# BumpSensors.net
KiCad netlist of a schematic drawn in Altium Designer
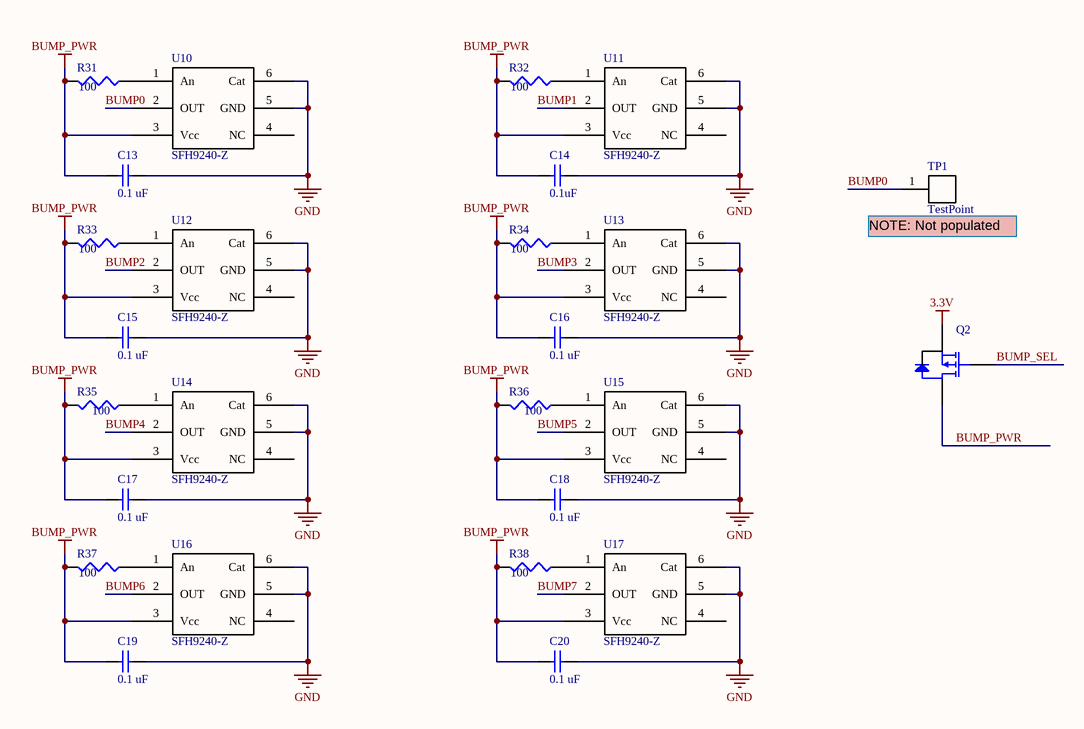
[diagram p0: BumpSensors.SchDoc]

(export (version "E")
  (design (tool "Eeschema 10.0.6"))
  (components
    (comp (ref "C13")
      (value "0.1 uF")
      (footprint "CAPC1005L")
      (description "Capacitor (Semiconductor SIM Model)")
      (fields (field (name "Comment") "Cap Semi") (field (name "PUBLISHER") "Altium Limited"))
      (libsource (lib "Miscellaneous Devices") (part "Cap Semi"))
    )
    (comp (ref "C14")
      (value "0.1uF")
      (footprint "CAPC1005L")
      (description "Capacitor (Semiconductor SIM Model)")
      (fields (field (name "Comment") "Cap Semi") (field (name "PUBLISHER") "Altium Limited"))
      (libsource (lib "Miscellaneous Devices") (part "Cap Semi"))
    )
    (comp (ref "C15")
      (value "0.1 uF")
      (footprint "CAPC1005L")
      (description "Capacitor (Semiconductor SIM Model)")
      (fields (field (name "Comment") "Cap Semi") (field (name "PUBLISHER") "Altium Limited"))
      (libsource (lib "Miscellaneous Devices") (part "Cap Semi"))
    )
    (comp (ref "C16")
      (value "0.1 uF")
      (footprint "CAPC1005L")
      (description "Capacitor (Semiconductor SIM Model)")
      (fields (field (name "Comment") "Cap Semi") (field (name "PUBLISHER") "Altium Limited"))
      (libsource (lib "Miscellaneous Devices") (part "Cap Semi"))
    )
    (comp (ref "C17")
      (value "0.1 uF")
      (footprint "CAPC1005L")
      (description "Capacitor (Semiconductor SIM Model)")
      (fields (field (name "Comment") "Cap Semi") (field (name "PUBLISHER") "Altium Limited"))
      (libsource (lib "Miscellaneous Devices") (part "Cap Semi"))
    )
    (comp (ref "C18")
      (value "0.1 uF")
      (footprint "CAPC1005L")
      (description "Capacitor (Semiconductor SIM Model)")
      (fields (field (name "Comment") "Cap Semi") (field (name "PUBLISHER") "Altium Limited"))
      (libsource (lib "Miscellaneous Devices") (part "Cap Semi"))
    )
    (comp (ref "C19")
      (value "0.1 uF")
      (footprint "CAPC1005L")
      (description "Capacitor (Semiconductor SIM Model)")
      (fields (field (name "Comment") "Cap Semi") (field (name "PUBLISHER") "Altium Limited"))
      (libsource (lib "Miscellaneous Devices") (part "Cap Semi"))
    )
    (comp (ref "C20")
      (value "0.1 uF")
      (footprint "CAPC1005L")
      (description "Capacitor (Semiconductor SIM Model)")
      (fields (field (name "Comment") "Cap Semi") (field (name "PUBLISHER") "Altium Limited"))
      (libsource (lib "Miscellaneous Devices") (part "Cap Semi"))
    )
    (comp (ref "Q2") (value "P-Mosfet") (footprint "SOT-23") (libsource (lib "mrone") (part "P-Mosfet")))
    (comp (ref "R31")
      (value "100")
      (footprint "RESC1608L")
      (description "Resistor")
      (fields (field (name "Comment") "Res3") (field (name "PUBLISHER") "Altium Limited"))
      (libsource (lib "Miscellaneous Devices") (part "Res3"))
    )
    (comp (ref "R32")
      (value "100")
      (footprint "RESC1608L")
      (description "Resistor")
      (fields (field (name "Comment") "Res3") (field (name "PUBLISHER") "Altium Limited"))
      (libsource (lib "Miscellaneous Devices") (part "Res3"))
    )
    (comp (ref "R33")
      (value "100")
      (footprint "RESC1608L")
      (description "Resistor")
      (fields (field (name "Comment") "Res3") (field (name "PUBLISHER") "Altium Limited"))
      (libsource (lib "Miscellaneous Devices") (part "Res3"))
    )
    (comp (ref "R34")
      (value "100")
      (footprint "RESC1608L")
      (description "Resistor")
      (fields (field (name "Comment") "Res3") (field (name "PUBLISHER") "Altium Limited"))
      (libsource (lib "Miscellaneous Devices") (part "Res3"))
    )
    (comp (ref "R35")
      (value "100")
      (footprint "RESC1608L")
      (description "Resistor")
      (fields (field (name "Comment") "Res3") (field (name "PUBLISHER") "Altium Limited"))
      (libsource (lib "Miscellaneous Devices") (part "Res3"))
    )
    (comp (ref "R36")
      (value "100")
      (footprint "RESC1608L")
      (description "Resistor")
      (fields (field (name "Comment") "Res3") (field (name "PUBLISHER") "Altium Limited"))
      (libsource (lib "Miscellaneous Devices") (part "Res3"))
    )
    (comp (ref "R37")
      (value "100")
      (footprint "RESC1608L")
      (description "Resistor")
      (fields (field (name "Comment") "Res3") (field (name "PUBLISHER") "Altium Limited"))
      (libsource (lib "Miscellaneous Devices") (part "Res3"))
    )
    (comp (ref "R38")
      (value "100")
      (footprint "RESC1608L")
      (description "Resistor")
      (fields (field (name "Comment") "Res3") (field (name "PUBLISHER") "Altium Limited"))
      (libsource (lib "Miscellaneous Devices") (part "Res3"))
    )
    (comp (ref "TP1")
      (value "TestPoint")
      (footprint "TestPoint")
      (libsource (lib "mrone") (part "TestPoint"))
    )
    (comp (ref "U10")
      (value "SFH9240-Z")
      (footprint "SFH9240-Z")
      (libsource (lib "mrone") (part "SFH9240-Z"))
    )
    (comp (ref "U11")
      (value "SFH9240-Z")
      (footprint "SFH9240-Z")
      (libsource (lib "mrone") (part "SFH9240-Z"))
    )
    (comp (ref "U12")
      (value "SFH9240-Z")
      (footprint "SFH9240-Z")
      (libsource (lib "mrone") (part "SFH9240-Z"))
    )
    (comp (ref "U13")
      (value "SFH9240-Z")
      (footprint "SFH9240-Z")
      (libsource (lib "mrone") (part "SFH9240-Z"))
    )
    (comp (ref "U14")
      (value "SFH9240-Z")
      (footprint "SFH9240-Z")
      (libsource (lib "mrone") (part "SFH9240-Z"))
    )
    (comp (ref "U15")
      (value "SFH9240-Z")
      (footprint "SFH9240-Z")
      (libsource (lib "mrone") (part "SFH9240-Z"))
    )
    (comp (ref "U16")
      (value "SFH9240-Z")
      (footprint "SFH9240-Z")
      (libsource (lib "mrone") (part "SFH9240-Z"))
    )
    (comp (ref "U17")
      (value "SFH9240-Z")
      (footprint "SFH9240-Z")
      (libsource (lib "mrone") (part "SFH9240-Z"))
    )
  )
  (nets
    (net (code "1") (name "/BUMP0") (class "Default")
      (node (ref "TP1") (pin "1") (pintype "passive"))
      (node (ref "U10") (pin "2") (pinfunction "OUT_2") (pintype "passive"))
    )
    (net (code "2") (name "/BUMP1") (class "Default")
      (node (ref "U11") (pin "2") (pinfunction "OUT_2") (pintype "passive"))
    )
    (net (code "3") (name "/BUMP2") (class "Default")
      (node (ref "U12") (pin "2") (pinfunction "OUT_2") (pintype "passive"))
    )
    (net (code "4") (name "/BUMP3") (class "Default")
      (node (ref "U13") (pin "2") (pinfunction "OUT_2") (pintype "passive"))
    )
    (net (code "5") (name "/BUMP4") (class "Default")
      (node (ref "U14") (pin "2") (pinfunction "OUT_2") (pintype "passive"))
    )
    (net (code "6") (name "/BUMP5") (class "Default")
      (node (ref "U15") (pin "2") (pinfunction "OUT_2") (pintype "passive"))
    )
    (net (code "7") (name "/BUMP6") (class "Default")
      (node (ref "U16") (pin "2") (pinfunction "OUT_2") (pintype "passive"))
    )
    (net (code "8") (name "/BUMP7") (class "Default")
      (node (ref "U17") (pin "2") (pinfunction "OUT_2") (pintype "passive"))
    )
    (net (code "9") (name "/BUMP_SEL") (class "Default")
      (node (ref "Q2") (pin "1") (pinfunction "G_1") (pintype "passive"))
    )
    (net (code "10") (name "3.3V") (class "Default")
      (node (ref "Q2") (pin "2") (pinfunction "S_2") (pintype "passive"))
    )
    (net (code "11") (name "BUMP_PWR") (class "Default")
      (node (ref "C13") (pin "2") (pinfunction "2_2") (pintype "passive"))
      (node (ref "C14") (pin "2") (pinfunction "2_2") (pintype "passive"))
      (node (ref "C15") (pin "2") (pinfunction "2_2") (pintype "passive"))
      (node (ref "C16") (pin "2") (pinfunction "2_2") (pintype "passive"))
      (node (ref "C17") (pin "2") (pinfunction "2_2") (pintype "passive"))
      (node (ref "C18") (pin "2") (pinfunction "2_2") (pintype "passive"))
      (node (ref "C19") (pin "2") (pinfunction "2_2") (pintype "passive"))
      (node (ref "C20") (pin "2") (pinfunction "2_2") (pintype "passive"))
      (node (ref "Q2") (pin "3") (pinfunction "D_3") (pintype "passive"))
      (node (ref "R31") (pin "2") (pinfunction "2_2") (pintype "passive"))
      (node (ref "R32") (pin "2") (pinfunction "2_2") (pintype "passive"))
      (node (ref "R33") (pin "2") (pinfunction "2_2") (pintype "passive"))
      (node (ref "R34") (pin "2") (pinfunction "2_2") (pintype "passive"))
      (node (ref "R35") (pin "2") (pinfunction "2_2") (pintype "passive"))
      (node (ref "R36") (pin "2") (pinfunction "2_2") (pintype "passive"))
      (node (ref "R37") (pin "2") (pinfunction "2_2") (pintype "passive"))
      (node (ref "R38") (pin "2") (pinfunction "2_2") (pintype "passive"))
      (node (ref "U10") (pin "3") (pinfunction "Vcc_3") (pintype "passive"))
      (node (ref "U11") (pin "3") (pinfunction "Vcc_3") (pintype "passive"))
      (node (ref "U12") (pin "3") (pinfunction "Vcc_3") (pintype "passive"))
      (node (ref "U13") (pin "3") (pinfunction "Vcc_3") (pintype "passive"))
      (node (ref "U14") (pin "3") (pinfunction "Vcc_3") (pintype "passive"))
      (node (ref "U15") (pin "3") (pinfunction "Vcc_3") (pintype "passive"))
      (node (ref "U16") (pin "3") (pinfunction "Vcc_3") (pintype "passive"))
      (node (ref "U17") (pin "3") (pinfunction "Vcc_3") (pintype "passive"))
    )
    (net (code "12") (name "GND") (class "Default")
      (node (ref "C13") (pin "1") (pinfunction "1_1") (pintype "passive"))
      (node (ref "C14") (pin "1") (pinfunction "1_1") (pintype "passive"))
      (node (ref "C15") (pin "1") (pinfunction "1_1") (pintype "passive"))
      (node (ref "C16") (pin "1") (pinfunction "1_1") (pintype "passive"))
      (node (ref "C17") (pin "1") (pinfunction "1_1") (pintype "passive"))
      (node (ref "C18") (pin "1") (pinfunction "1_1") (pintype "passive"))
      (node (ref "C19") (pin "1") (pinfunction "1_1") (pintype "passive"))
      (node (ref "C20") (pin "1") (pinfunction "1_1") (pintype "passive"))
      (node (ref "U10") (pin "5") (pinfunction "GND_5") (pintype "passive"))
      (node (ref "U10") (pin "6") (pinfunction "Cat_6") (pintype "passive"))
      (node (ref "U11") (pin "5") (pinfunction "GND_5") (pintype "passive"))
      (node (ref "U11") (pin "6") (pinfunction "Cat_6") (pintype "passive"))
      (node (ref "U12") (pin "5") (pinfunction "GND_5") (pintype "passive"))
      (node (ref "U12") (pin "6") (pinfunction "Cat_6") (pintype "passive"))
      (node (ref "U13") (pin "5") (pinfunction "GND_5") (pintype "passive"))
      (node (ref "U13") (pin "6") (pinfunction "Cat_6") (pintype "passive"))
      (node (ref "U14") (pin "5") (pinfunction "GND_5") (pintype "passive"))
      (node (ref "U14") (pin "6") (pinfunction "Cat_6") (pintype "passive"))
      (node (ref "U15") (pin "5") (pinfunction "GND_5") (pintype "passive"))
      (node (ref "U15") (pin "6") (pinfunction "Cat_6") (pintype "passive"))
      (node (ref "U16") (pin "5") (pinfunction "GND_5") (pintype "passive"))
      (node (ref "U16") (pin "6") (pinfunction "Cat_6") (pintype "passive"))
      (node (ref "U17") (pin "5") (pinfunction "GND_5") (pintype "passive"))
      (node (ref "U17") (pin "6") (pinfunction "Cat_6") (pintype "passive"))
    )
    (net (code "13") (name "Net-(U10-An)") (class "Default")
      (node (ref "R31") (pin "1") (pinfunction "1_1") (pintype "passive"))
      (node (ref "U10") (pin "1") (pinfunction "An_1") (pintype "passive"))
    )
    (net (code "14") (name "Net-(U11-An)") (class "Default")
      (node (ref "R32") (pin "1") (pinfunction "1_1") (pintype "passive"))
      (node (ref "U11") (pin "1") (pinfunction "An_1") (pintype "passive"))
    )
    (net (code "15") (name "Net-(U12-An)") (class "Default")
      (node (ref "R33") (pin "1") (pinfunction "1_1") (pintype "passive"))
      (node (ref "U12") (pin "1") (pinfunction "An_1") (pintype "passive"))
    )
    (net (code "16") (name "Net-(U13-An)") (class "Default")
      (node (ref "R34") (pin "1") (pinfunction "1_1") (pintype "passive"))
      (node (ref "U13") (pin "1") (pinfunction "An_1") (pintype "passive"))
    )
    (net (code "17") (name "Net-(U14-An)") (class "Default")
      (node (ref "R35") (pin "1") (pinfunction "1_1") (pintype "passive"))
      (node (ref "U14") (pin "1") (pinfunction "An_1") (pintype "passive"))
    )
    (net (code "18") (name "Net-(U15-An)") (class "Default")
      (node (ref "R36") (pin "1") (pinfunction "1_1") (pintype "passive"))
      (node (ref "U15") (pin "1") (pinfunction "An_1") (pintype "passive"))
    )
    (net (code "19") (name "Net-(U16-An)") (class "Default")
      (node (ref "R37") (pin "1") (pinfunction "1_1") (pintype "passive"))
      (node (ref "U16") (pin "1") (pinfunction "An_1") (pintype "passive"))
    )
    (net (code "20") (name "Net-(U17-An)") (class "Default")
      (node (ref "R38") (pin "1") (pinfunction "1_1") (pintype "passive"))
      (node (ref "U17") (pin "1") (pinfunction "An_1") (pintype "passive"))
    )
    (net (code "21") (name "unconnected-(U10-NC-Pad4)") (class "Default")
      (node (ref "U10") (pin "4") (pinfunction "NC_4") (pintype "passive"))
    )
    (net (code "22") (name "unconnected-(U11-NC-Pad4)") (class "Default")
      (node (ref "U11") (pin "4") (pinfunction "NC_4") (pintype "passive"))
    )
    (net (code "23") (name "unconnected-(U12-NC-Pad4)") (class "Default")
      (node (ref "U12") (pin "4") (pinfunction "NC_4") (pintype "passive"))
    )
    (net (code "24") (name "unconnected-(U13-NC-Pad4)") (class "Default")
      (node (ref "U13") (pin "4") (pinfunction "NC_4") (pintype "passive"))
    )
    (net (code "25") (name "unconnected-(U14-NC-Pad4)") (class "Default")
      (node (ref "U14") (pin "4") (pinfunction "NC_4") (pintype "passive"))
    )
    (net (code "26") (name "unconnected-(U15-NC-Pad4)") (class "Default")
      (node (ref "U15") (pin "4") (pinfunction "NC_4") (pintype "passive"))
    )
    (net (code "27") (name "unconnected-(U16-NC-Pad4)") (class "Default")
      (node (ref "U16") (pin "4") (pinfunction "NC_4") (pintype "passive"))
    )
    (net (code "28") (name "unconnected-(U17-NC-Pad4)") (class "Default")
      (node (ref "U17") (pin "4") (pinfunction "NC_4") (pintype "passive"))
    )
  )
)
